# MOS.net
KiCad netlist of a schematic drawn in Altium Designer
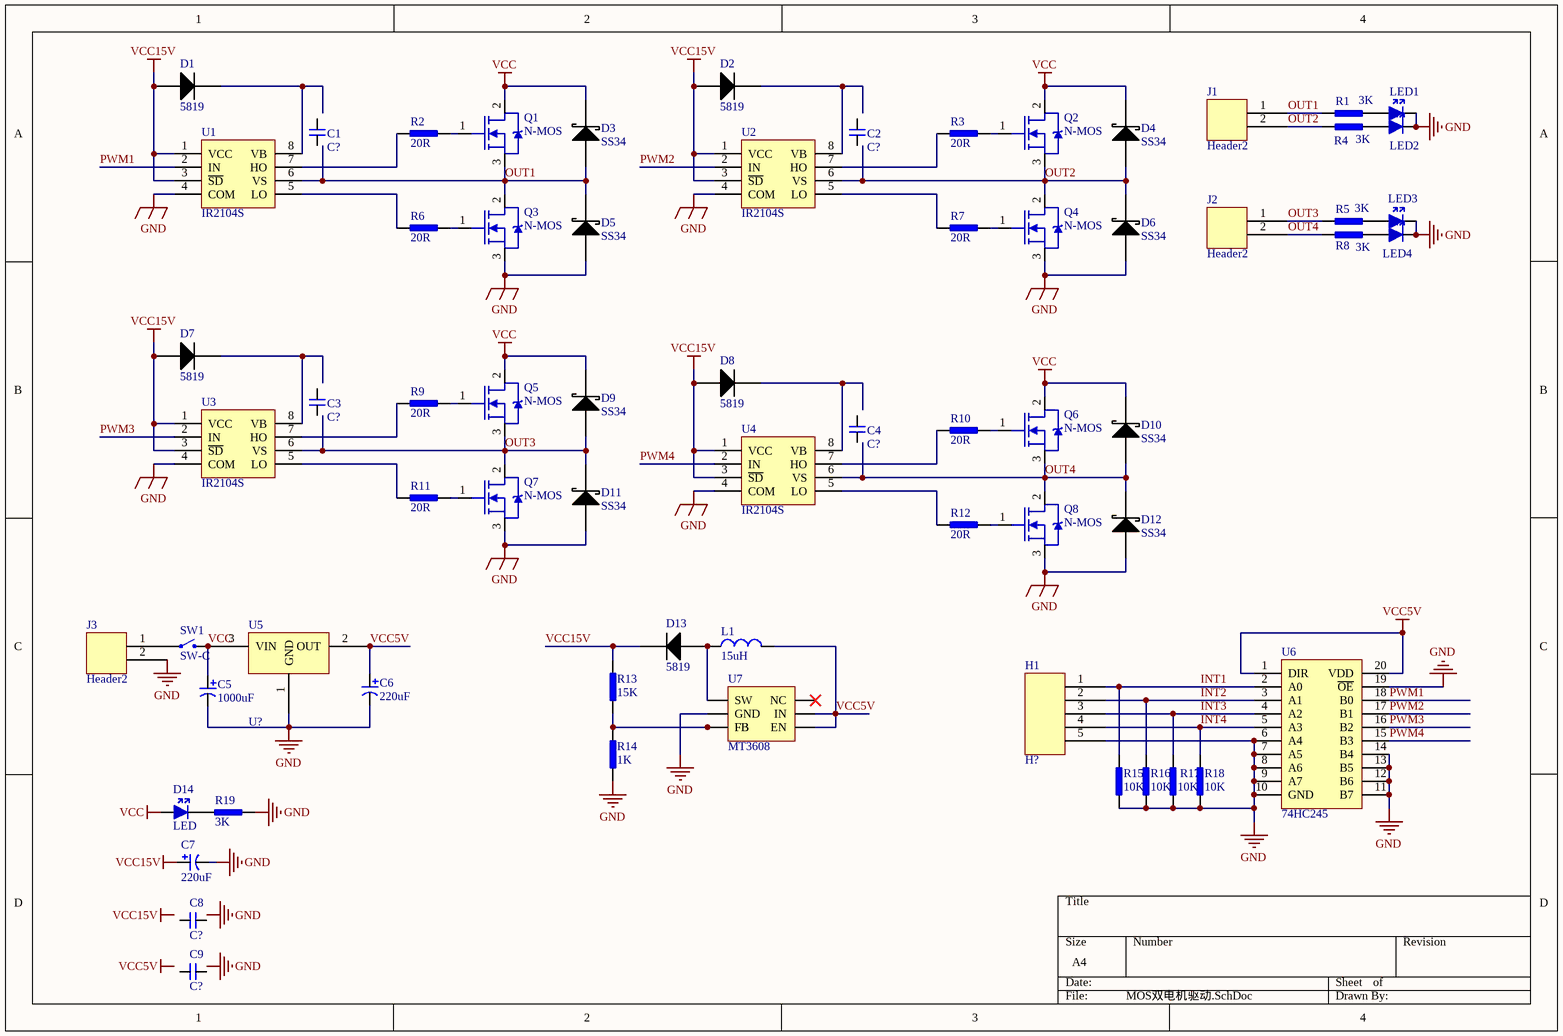
[diagram p0: MOS双电机驱动.SchDoc]

(export (version "E")
  (design (tool "Eeschema 10.0.6"))
  (components
    (comp (ref "C1") (value "C?") (footprint "C 0805") (libsource (lib "常用原理图库") (part "CAP")))
    (comp (ref "C2") (value "C?") (footprint "C 0805") (libsource (lib "常用原理图库") (part "CAP")))
    (comp (ref "C3") (value "C?") (footprint "C 0805") (libsource (lib "常用原理图库") (part "CAP")))
    (comp (ref "C4") (value "C?") (footprint "C 0805") (libsource (lib "常用原理图库") (part "CAP")))
    (comp (ref "C5") (value "1000uF") (footprint "直插电解电容10") (libsource (lib "常用原理图库") (part "CAP-SMD")))
    (comp (ref "C6") (value "220uF") (footprint "CAP6.6X6.6") (libsource (lib "常用原理图库") (part "CAP-SMD")))
    (comp (ref "C7") (value "220uF") (footprint "CAP6.6X6.6") (libsource (lib "常用原理图库") (part "CAP-SMD")))
    (comp (ref "C8") (value "C?") (footprint "C 0805") (libsource (lib "常用原理图库") (part "CAP")))
    (comp (ref "C9") (value "C?") (footprint "C 0805") (libsource (lib "常用原理图库") (part "CAP")))
    (comp (ref "D1") (value "5819") (footprint "D1206") (libsource (lib "MOS电机驱动") (part "D1206")))
    (comp (ref "D2") (value "5819") (footprint "D1206") (libsource (lib "MOS电机驱动") (part "D1206")))
    (comp (ref "D3")
      (value "SS34")
      (footprint "SMA")
      (description "肖特基二极管")
      (libsource (lib "常用原理图库") (part "D-SMA"))
    )
    (comp (ref "D4")
      (value "SS34")
      (footprint "SMA")
      (description "肖特基二极管")
      (libsource (lib "常用原理图库") (part "D-SMA"))
    )
    (comp (ref "D5")
      (value "SS34")
      (footprint "SMA")
      (description "肖特基二极管")
      (libsource (lib "常用原理图库") (part "D-SMA"))
    )
    (comp (ref "D6")
      (value "SS34")
      (footprint "SMA")
      (description "肖特基二极管")
      (libsource (lib "常用原理图库") (part "D-SMA"))
    )
    (comp (ref "D7") (value "5819") (footprint "D1206") (libsource (lib "MOS电机驱动") (part "D1206")))
    (comp (ref "D8") (value "5819") (footprint "D1206") (libsource (lib "MOS电机驱动") (part "D1206")))
    (comp (ref "D9")
      (value "SS34")
      (footprint "SMA")
      (description "肖特基二极管")
      (libsource (lib "常用原理图库") (part "D-SMA"))
    )
    (comp (ref "D10")
      (value "SS34")
      (footprint "SMA")
      (description "肖特基二极管")
      (libsource (lib "常用原理图库") (part "D-SMA"))
    )
    (comp (ref "D11")
      (value "SS34")
      (footprint "SMA")
      (description "肖特基二极管")
      (libsource (lib "常用原理图库") (part "D-SMA"))
    )
    (comp (ref "D12")
      (value "SS34")
      (footprint "SMA")
      (description "肖特基二极管")
      (libsource (lib "常用原理图库") (part "D-SMA"))
    )
    (comp (ref "D13") (value "5819") (footprint "D1206") (libsource (lib "MOS电机驱动") (part "D1206")))
    (comp (ref "D14") (value "LED") (footprint "0805LED") (libsource (lib "常用原理图库") (part "LED")))
    (comp (ref "H1") (value "H?") (footprint "SIP05") (libsource (lib "常用原理图库") (part "header5")))
    (comp (ref "J1") (value "Header2") (footprint "2PIN-5.08B") (libsource (lib "常用原理图库") (part "Header2")))
    (comp (ref "J2") (value "Header2") (footprint "2PIN-5.08B") (libsource (lib "常用原理图库") (part "Header2")))
    (comp (ref "J3") (value "Header2") (footprint "2PIN-5.08B") (libsource (lib "常用原理图库") (part "Header2")))
    (comp (ref "L1") (value "15uH") (footprint "L-06030") (libsource (lib "常用原理图库") (part "Inductance")))
    (comp (ref "LED1") (value "LED") (footprint "0805LED") (libsource (lib "常用原理图库") (part "LED")))
    (comp (ref "LED2") (value "LED") (footprint "0805LED") (libsource (lib "常用原理图库") (part "LED")))
    (comp (ref "LED3") (value "LED") (footprint "0805LED") (libsource (lib "常用原理图库") (part "LED")))
    (comp (ref "LED4") (value "LED") (footprint "0805LED") (libsource (lib "常用原理图库") (part "LED")))
    (comp (ref "Q1") (value "N-MOS") (footprint "常用封装:TO-252") (libsource (lib "常用原理图库") (part "N-MOS")))
    (comp (ref "Q2") (value "N-MOS") (footprint "常用封装:TO-252") (libsource (lib "常用原理图库") (part "N-MOS")))
    (comp (ref "Q3") (value "N-MOS") (footprint "常用封装:TO-252") (libsource (lib "常用原理图库") (part "N-MOS")))
    (comp (ref "Q4") (value "N-MOS") (footprint "常用封装:TO-252") (libsource (lib "常用原理图库") (part "N-MOS")))
    (comp (ref "Q5") (value "N-MOS") (footprint "常用封装:TO-252") (libsource (lib "常用原理图库") (part "N-MOS")))
    (comp (ref "Q6") (value "N-MOS") (footprint "常用封装:TO-252") (libsource (lib "常用原理图库") (part "N-MOS")))
    (comp (ref "Q7") (value "N-MOS") (footprint "常用封装:TO-252") (libsource (lib "常用原理图库") (part "N-MOS")))
    (comp (ref "Q8") (value "N-MOS") (footprint "常用封装:TO-252") (libsource (lib "常用原理图库") (part "N-MOS")))
    (comp (ref "R1") (value "3K") (footprint "R 0805") (libsource (lib "常用原理图库") (part "RES")))
    (comp (ref "R2") (value "20R") (footprint "R 0805") (libsource (lib "常用原理图库") (part "RES")))
    (comp (ref "R3") (value "20R") (footprint "R 0805") (libsource (lib "常用原理图库") (part "RES")))
    (comp (ref "R4") (value "3K") (footprint "R 0805") (libsource (lib "常用原理图库") (part "RES")))
    (comp (ref "R5") (value "3K") (footprint "R 0805") (libsource (lib "常用原理图库") (part "RES")))
    (comp (ref "R6") (value "20R") (footprint "R 0805") (libsource (lib "常用原理图库") (part "RES")))
    (comp (ref "R7") (value "20R") (footprint "R 0805") (libsource (lib "常用原理图库") (part "RES")))
    (comp (ref "R8") (value "3K") (footprint "R 0805") (libsource (lib "常用原理图库") (part "RES")))
    (comp (ref "R9") (value "20R") (footprint "R 0805") (libsource (lib "常用原理图库") (part "RES")))
    (comp (ref "R10") (value "20R") (footprint "R 0805") (libsource (lib "常用原理图库") (part "RES")))
    (comp (ref "R11") (value "20R") (footprint "R 0805") (libsource (lib "常用原理图库") (part "RES")))
    (comp (ref "R12") (value "20R") (footprint "R 0805") (libsource (lib "常用原理图库") (part "RES")))
    (comp (ref "R13") (value "15K") (footprint "R 0805") (libsource (lib "") (part "RES_1")))
    (comp (ref "R14") (value "1K") (footprint "R 0805") (libsource (lib "") (part "RES_1")))
    (comp (ref "R15") (value "10K") (footprint "R 0805") (libsource (lib "") (part "RES_1")))
    (comp (ref "R16") (value "10K") (footprint "R 0805") (libsource (lib "") (part "RES_1")))
    (comp (ref "R17") (value "10K") (footprint "R 0805") (libsource (lib "") (part "RES_1")))
    (comp (ref "R18") (value "10K") (footprint "R 0805") (libsource (lib "") (part "RES_1")))
    (comp (ref "R19") (value "3K") (footprint "R 0805") (libsource (lib "常用原理图库") (part "RES")))
    (comp (ref "SW1") (value "SW-C") (footprint "SW-TO3") (libsource (lib "常用原理图库") (part "SW-C")))
    (comp (ref "U1")
      (value "IR2104S")
      (footprint "SOP-8")
      (description "半桥驱动器")
      (libsource (lib "MOS电机驱动") (part "IR2104S"))
    )
    (comp (ref "U2")
      (value "IR2104S")
      (footprint "SOP-8")
      (description "半桥驱动器")
      (libsource (lib "MOS电机驱动") (part "IR2104S"))
    )
    (comp (ref "U3")
      (value "IR2104S")
      (footprint "SOP-8")
      (description "半桥驱动器")
      (libsource (lib "MOS电机驱动") (part "IR2104S"))
    )
    (comp (ref "U4")
      (value "IR2104S")
      (footprint "SOP-8")
      (description "半桥驱动器")
      (libsource (lib "MOS电机驱动") (part "IR2104S"))
    )
    (comp (ref "U5") (value "U?") (footprint "SOT223") (libsource (lib "常用原理图库") (part "1117")))
    (comp (ref "U6") (value "74HC245") (footprint "TSSOP-20") (libsource (lib "常用原理图库") (part "74HC245")))
    (comp (ref "U7") (value "MT3608") (footprint "SOT23-6") (libsource (lib "常用原理图库") (part "MT3608")))
  )
  (nets
    (net (code "1") (name "/INT1") (class "Default")
      (node (ref "H1") (pin "1") (pintype "passive"))
      (node (ref "R15") (pin "2") (pintype "passive"))
      (node (ref "U6") (pin "2") (pinfunction "A0_2") (pintype "passive"))
    )
    (net (code "2") (name "/INT2") (class "Default")
      (node (ref "H1") (pin "2") (pintype "passive"))
      (node (ref "R16") (pin "2") (pintype "passive"))
      (node (ref "U6") (pin "3") (pinfunction "A1_3") (pintype "passive"))
    )
    (net (code "3") (name "/INT3") (class "Default")
      (node (ref "H1") (pin "3") (pintype "passive"))
      (node (ref "R17") (pin "2") (pintype "passive"))
      (node (ref "U6") (pin "4") (pinfunction "A2_4") (pintype "passive"))
    )
    (net (code "4") (name "/INT4") (class "Default")
      (node (ref "H1") (pin "4") (pintype "passive"))
      (node (ref "R18") (pin "2") (pintype "passive"))
      (node (ref "U6") (pin "5") (pinfunction "A3_5") (pintype "passive"))
    )
    (net (code "5") (name "/OUT1") (class "Default")
      (node (ref "D3") (pin "1") (pinfunction "1_1") (pintype "passive"))
      (node (ref "D5") (pin "2") (pinfunction "2_2") (pintype "passive"))
      (node (ref "J1") (pin "1") (pintype "passive"))
      (node (ref "Q1") (pin "3") (pintype "passive"))
      (node (ref "Q3") (pin "2") (pintype "passive"))
      (node (ref "R1") (pin "1") (pintype "passive"))
      (node (ref "U1") (pin "6") (pinfunction "VS_6") (pintype "passive"))
    )
    (net (code "6") (name "/OUT2") (class "Default")
      (node (ref "D4") (pin "1") (pinfunction "1_1") (pintype "passive"))
      (node (ref "D6") (pin "2") (pinfunction "2_2") (pintype "passive"))
      (node (ref "J1") (pin "2") (pintype "passive"))
      (node (ref "Q2") (pin "3") (pintype "passive"))
      (node (ref "Q4") (pin "2") (pintype "passive"))
      (node (ref "R4") (pin "1") (pintype "passive"))
      (node (ref "U2") (pin "6") (pinfunction "VS_6") (pintype "passive"))
    )
    (net (code "7") (name "/OUT3") (class "Default")
      (node (ref "D11") (pin "2") (pinfunction "2_2") (pintype "passive"))
      (node (ref "D9") (pin "1") (pinfunction "1_1") (pintype "passive"))
      (node (ref "J2") (pin "1") (pintype "passive"))
      (node (ref "Q5") (pin "3") (pintype "passive"))
      (node (ref "Q7") (pin "2") (pintype "passive"))
      (node (ref "R5") (pin "1") (pintype "passive"))
      (node (ref "U3") (pin "6") (pinfunction "VS_6") (pintype "passive"))
    )
    (net (code "8") (name "/OUT4") (class "Default")
      (node (ref "D10") (pin "1") (pinfunction "1_1") (pintype "passive"))
      (node (ref "D12") (pin "2") (pinfunction "2_2") (pintype "passive"))
      (node (ref "J2") (pin "2") (pintype "passive"))
      (node (ref "Q6") (pin "3") (pintype "passive"))
      (node (ref "Q8") (pin "2") (pintype "passive"))
      (node (ref "R8") (pin "1") (pintype "passive"))
      (node (ref "U4") (pin "6") (pinfunction "VS_6") (pintype "passive"))
    )
    (net (code "9") (name "/PWM1") (class "Default")
      (node (ref "U1") (pin "2") (pinfunction "IN_2") (pintype "passive"))
      (node (ref "U6") (pin "18") (pinfunction "B0_18") (pintype "passive"))
    )
    (net (code "10") (name "/PWM2") (class "Default")
      (node (ref "U2") (pin "2") (pinfunction "IN_2") (pintype "passive"))
      (node (ref "U6") (pin "17") (pinfunction "B1_17") (pintype "passive"))
    )
    (net (code "11") (name "/PWM3") (class "Default")
      (node (ref "U3") (pin "2") (pinfunction "IN_2") (pintype "passive"))
      (node (ref "U6") (pin "16") (pinfunction "B2_16") (pintype "passive"))
    )
    (net (code "12") (name "/PWM4") (class "Default")
      (node (ref "U4") (pin "2") (pinfunction "IN_2") (pintype "passive"))
      (node (ref "U6") (pin "15") (pinfunction "B3_15") (pintype "passive"))
    )
    (net (code "13") (name "GND") (class "Default")
      (node (ref "C5") (pin "1") (pintype "passive"))
      (node (ref "C6") (pin "1") (pintype "passive"))
      (node (ref "C7") (pin "1") (pintype "passive"))
      (node (ref "D11") (pin "1") (pinfunction "1_1") (pintype "passive"))
      (node (ref "D12") (pin "1") (pinfunction "1_1") (pintype "passive"))
      (node (ref "D5") (pin "1") (pinfunction "1_1") (pintype "passive"))
      (node (ref "D6") (pin "1") (pinfunction "1_1") (pintype "passive"))
      (node (ref "H1") (pin "5") (pintype "passive"))
      (node (ref "J3") (pin "2") (pintype "passive"))
      (node (ref "LED1") (pin "2") (pintype "passive"))
      (node (ref "LED2") (pin "2") (pintype "passive"))
      (node (ref "LED3") (pin "2") (pintype "passive"))
      (node (ref "LED4") (pin "2") (pintype "passive"))
      (node (ref "Q3") (pin "3") (pintype "passive"))
      (node (ref "Q4") (pin "3") (pintype "passive"))
      (node (ref "Q7") (pin "3") (pintype "passive"))
      (node (ref "Q8") (pin "3") (pintype "passive"))
      (node (ref "R14") (pin "1") (pintype "passive"))
      (node (ref "R15") (pin "1") (pintype "passive"))
      (node (ref "R16") (pin "1") (pintype "passive"))
      (node (ref "R17") (pin "1") (pintype "passive"))
      (node (ref "R18") (pin "1") (pintype "passive"))
      (node (ref "R19") (pin "2") (pintype "passive"))
      (node (ref "U1") (pin "4") (pinfunction "COM_4") (pintype "passive"))
      (node (ref "U2") (pin "4") (pinfunction "COM_4") (pintype "passive"))
      (node (ref "U3") (pin "4") (pinfunction "COM_4") (pintype "passive"))
      (node (ref "U4") (pin "4") (pinfunction "COM_4") (pintype "passive"))
      (node (ref "U5") (pin "1") (pinfunction "GND_1") (pintype "passive"))
      (node (ref "U6") (pin "10") (pinfunction "GND_10") (pintype "passive"))
      (node (ref "U6") (pin "11") (pinfunction "B7_11") (pintype "passive"))
      (node (ref "U6") (pin "12") (pinfunction "B6_12") (pintype "passive"))
      (node (ref "U6") (pin "13") (pinfunction "B5_13") (pintype "passive"))
      (node (ref "U6") (pin "14") (pinfunction "B4_14") (pintype "passive"))
      (node (ref "U6") (pin "19") (pinfunction "~{OE}_19") (pintype "passive"))
      (node (ref "U6") (pin "6") (pinfunction "A4_6") (pintype "passive"))
      (node (ref "U6") (pin "7") (pinfunction "A5_7") (pintype "passive"))
      (node (ref "U6") (pin "8") (pinfunction "A6_8") (pintype "passive"))
      (node (ref "U6") (pin "9") (pinfunction "A7_9") (pintype "passive"))
      (node (ref "U7") (pin "2") (pinfunction "GND_2") (pintype "passive"))
    )
    (net (code "14") (name "Net-(D14-Pad2)") (class "Default")
      (node (ref "D14") (pin "2") (pintype "passive"))
      (node (ref "R19") (pin "1") (pintype "passive"))
    )
    (net (code "15") (name "Net-(J3-Pad1)") (class "Default")
      (node (ref "J3") (pin "1") (pintype "passive"))
      (node (ref "SW1") (pin "1") (pintype "passive"))
    )
    (net (code "16") (name "Net-(LED1-Pad1)") (class "Default")
      (node (ref "LED1") (pin "1") (pintype "passive"))
      (node (ref "R1") (pin "2") (pintype "passive"))
    )
    (net (code "17") (name "Net-(LED2-Pad1)") (class "Default")
      (node (ref "LED2") (pin "1") (pintype "passive"))
      (node (ref "R4") (pin "2") (pintype "passive"))
    )
    (net (code "18") (name "Net-(LED3-Pad1)") (class "Default")
      (node (ref "LED3") (pin "1") (pintype "passive"))
      (node (ref "R5") (pin "2") (pintype "passive"))
    )
    (net (code "19") (name "Net-(LED4-Pad1)") (class "Default")
      (node (ref "LED4") (pin "1") (pintype "passive"))
      (node (ref "R8") (pin "2") (pintype "passive"))
    )
    (net (code "20") (name "Net-(Q1-Pad1)") (class "Default")
      (node (ref "Q1") (pin "1") (pintype "passive"))
      (node (ref "R2") (pin "2") (pintype "passive"))
    )
    (net (code "21") (name "Net-(Q2-Pad1)") (class "Default")
      (node (ref "Q2") (pin "1") (pintype "passive"))
      (node (ref "R3") (pin "2") (pintype "passive"))
    )
    (net (code "22") (name "Net-(Q3-Pad1)") (class "Default")
      (node (ref "Q3") (pin "1") (pintype "passive"))
      (node (ref "R6") (pin "2") (pintype "passive"))
    )
    (net (code "23") (name "Net-(Q4-Pad1)") (class "Default")
      (node (ref "Q4") (pin "1") (pintype "passive"))
      (node (ref "R7") (pin "2") (pintype "passive"))
    )
    (net (code "24") (name "Net-(Q5-Pad1)") (class "Default")
      (node (ref "Q5") (pin "1") (pintype "passive"))
      (node (ref "R9") (pin "2") (pintype "passive"))
    )
    (net (code "25") (name "Net-(Q6-Pad1)") (class "Default")
      (node (ref "Q6") (pin "1") (pintype "passive"))
      (node (ref "R10") (pin "2") (pintype "passive"))
    )
    (net (code "26") (name "Net-(Q7-Pad1)") (class "Default")
      (node (ref "Q7") (pin "1") (pintype "passive"))
      (node (ref "R11") (pin "2") (pintype "passive"))
    )
    (net (code "27") (name "Net-(Q8-Pad1)") (class "Default")
      (node (ref "Q8") (pin "1") (pintype "passive"))
      (node (ref "R12") (pin "2") (pintype "passive"))
    )
    (net (code "28") (name "Net-(R13-Pad1)") (class "Default")
      (node (ref "R13") (pin "1") (pintype "passive"))
      (node (ref "R14") (pin "2") (pintype "passive"))
      (node (ref "U7") (pin "3") (pinfunction "FB_3") (pintype "passive"))
      (node (ref "U7") (pin "4") (pinfunction "FB_4") (pintype "passive"))
    )
    (net (code "29") (name "Net-(U1-HO)") (class "Default")
      (node (ref "R2") (pin "1") (pintype "passive"))
      (node (ref "U1") (pin "7") (pinfunction "HO_7") (pintype "passive"))
    )
    (net (code "30") (name "Net-(U1-LO)") (class "Default")
      (node (ref "R6") (pin "1") (pintype "passive"))
      (node (ref "U1") (pin "5") (pinfunction "LO_5") (pintype "passive"))
    )
    (net (code "31") (name "Net-(U1-VB)") (class "Default")
      (node (ref "D1") (pin "2") (pinfunction "2_2") (pintype "passive"))
      (node (ref "U1") (pin "8") (pinfunction "VB_8") (pintype "passive"))
    )
    (net (code "32") (name "Net-(U2-HO)") (class "Default")
      (node (ref "R3") (pin "1") (pintype "passive"))
      (node (ref "U2") (pin "7") (pinfunction "HO_7") (pintype "passive"))
    )
    (net (code "33") (name "Net-(U2-LO)") (class "Default")
      (node (ref "R7") (pin "1") (pintype "passive"))
      (node (ref "U2") (pin "5") (pinfunction "LO_5") (pintype "passive"))
    )
    (net (code "34") (name "Net-(U2-VB)") (class "Default")
      (node (ref "D2") (pin "2") (pinfunction "2_2") (pintype "passive"))
      (node (ref "U2") (pin "8") (pinfunction "VB_8") (pintype "passive"))
    )
    (net (code "35") (name "Net-(U3-HO)") (class "Default")
      (node (ref "R9") (pin "1") (pintype "passive"))
      (node (ref "U3") (pin "7") (pinfunction "HO_7") (pintype "passive"))
    )
    (net (code "36") (name "Net-(U3-LO)") (class "Default")
      (node (ref "R11") (pin "1") (pintype "passive"))
      (node (ref "U3") (pin "5") (pinfunction "LO_5") (pintype "passive"))
    )
    (net (code "37") (name "Net-(U3-VB)") (class "Default")
      (node (ref "D7") (pin "2") (pinfunction "2_2") (pintype "passive"))
      (node (ref "U3") (pin "8") (pinfunction "VB_8") (pintype "passive"))
    )
    (net (code "38") (name "Net-(U4-HO)") (class "Default")
      (node (ref "R10") (pin "1") (pintype "passive"))
      (node (ref "U4") (pin "7") (pinfunction "HO_7") (pintype "passive"))
    )
    (net (code "39") (name "Net-(U4-LO)") (class "Default")
      (node (ref "R12") (pin "1") (pintype "passive"))
      (node (ref "U4") (pin "5") (pinfunction "LO_5") (pintype "passive"))
    )
    (net (code "40") (name "Net-(U4-VB)") (class "Default")
      (node (ref "D8") (pin "2") (pinfunction "2_2") (pintype "passive"))
      (node (ref "U4") (pin "8") (pinfunction "VB_8") (pintype "passive"))
    )
    (net (code "41") (name "Net-(U7-SW)") (class "Default")
      (node (ref "D13") (pin "1") (pinfunction "1_1") (pintype "passive"))
      (node (ref "L1") (pin "2") (pinfunction "2_2") (pintype "passive"))
      (node (ref "U7") (pin "1") (pinfunction "SW_1") (pintype "passive"))
    )
    (net (code "42") (name "VCC") (class "Default")
      (node (ref "C5") (pin "2") (pintype "passive"))
      (node (ref "D10") (pin "2") (pinfunction "2_2") (pintype "passive"))
      (node (ref "D14") (pin "1") (pintype "passive"))
      (node (ref "D3") (pin "2") (pinfunction "2_2") (pintype "passive"))
      (node (ref "D4") (pin "2") (pinfunction "2_2") (pintype "passive"))
      (node (ref "D9") (pin "2") (pinfunction "2_2") (pintype "passive"))
      (node (ref "Q1") (pin "2") (pintype "passive"))
      (node (ref "Q2") (pin "2") (pintype "passive"))
      (node (ref "Q5") (pin "2") (pintype "passive"))
      (node (ref "Q6") (pin "2") (pintype "passive"))
      (node (ref "SW1") (pin "2") (pintype "passive"))
      (node (ref "U5") (pin "3") (pinfunction "VIN_3") (pintype "passive"))
    )
    (net (code "43") (name "VCC5V") (class "Default")
      (node (ref "C6") (pin "2") (pintype "passive"))
      (node (ref "L1") (pin "1") (pinfunction "1_1") (pintype "passive"))
      (node (ref "U5") (pin "2") (pinfunction "OUT_2") (pintype "passive"))
      (node (ref "U6") (pin "1") (pinfunction "DIR_1") (pintype "passive"))
      (node (ref "U6") (pin "20") (pinfunction "VDD_20") (pintype "passive"))
      (node (ref "U7") (pin "4") (pinfunction "EN_4") (pintype "passive"))
      (node (ref "U7") (pin "5") (pinfunction "IN_5") (pintype "passive"))
    )
    (net (code "44") (name "VCC15V") (class "Default")
      (node (ref "C7") (pin "2") (pintype "passive"))
      (node (ref "D1") (pin "1") (pinfunction "1_1") (pintype "passive"))
      (node (ref "D13") (pin "2") (pinfunction "2_2") (pintype "passive"))
      (node (ref "D2") (pin "1") (pinfunction "1_1") (pintype "passive"))
      (node (ref "D7") (pin "1") (pinfunction "1_1") (pintype "passive"))
      (node (ref "D8") (pin "1") (pinfunction "1_1") (pintype "passive"))
      (node (ref "R13") (pin "2") (pintype "passive"))
      (node (ref "U1") (pin "1") (pinfunction "VCC_1") (pintype "passive"))
      (node (ref "U1") (pin "3") (pinfunction "~{SD}_3") (pintype "passive"))
      (node (ref "U2") (pin "1") (pinfunction "VCC_1") (pintype "passive"))
      (node (ref "U2") (pin "3") (pinfunction "~{SD}_3") (pintype "passive"))
      (node (ref "U3") (pin "1") (pinfunction "VCC_1") (pintype "passive"))
      (node (ref "U3") (pin "3") (pinfunction "~{SD}_3") (pintype "passive"))
      (node (ref "U4") (pin "1") (pinfunction "VCC_1") (pintype "passive"))
      (node (ref "U4") (pin "3") (pinfunction "~{SD}_3") (pintype "passive"))
    )
    (net (code "45") (name "unconnected-(C1-Pad1)") (class "Default")
      (node (ref "C1") (pin "1") (pintype "passive"))
    )
    (net (code "46") (name "unconnected-(C1-Pad2)") (class "Default")
      (node (ref "C1") (pin "2") (pintype "passive"))
    )
    (net (code "47") (name "unconnected-(C2-Pad1)") (class "Default")
      (node (ref "C2") (pin "1") (pintype "passive"))
    )
    (net (code "48") (name "unconnected-(C2-Pad2)") (class "Default")
      (node (ref "C2") (pin "2") (pintype "passive"))
    )
    (net (code "49") (name "unconnected-(C3-Pad1)") (class "Default")
      (node (ref "C3") (pin "1") (pintype "passive"))
    )
    (net (code "50") (name "unconnected-(C3-Pad2)") (class "Default")
      (node (ref "C3") (pin "2") (pintype "passive"))
    )
    (net (code "51") (name "unconnected-(C4-Pad1)") (class "Default")
      (node (ref "C4") (pin "1") (pintype "passive"))
    )
    (net (code "52") (name "unconnected-(C4-Pad2)") (class "Default")
      (node (ref "C4") (pin "2") (pintype "passive"))
    )
    (net (code "53") (name "unconnected-(C8-Pad1)") (class "Default")
      (node (ref "C8") (pin "1") (pintype "passive"))
    )
    (net (code "54") (name "unconnected-(C8-Pad2)") (class "Default")
      (node (ref "C8") (pin "2") (pintype "passive"))
    )
    (net (code "55") (name "unconnected-(C9-Pad1)") (class "Default")
      (node (ref "C9") (pin "1") (pintype "passive"))
    )
    (net (code "56") (name "unconnected-(C9-Pad2)") (class "Default")
      (node (ref "C9") (pin "2") (pintype "passive"))
    )
    (net (code "57") (name "unconnected-(U7-NC-Pad6)") (class "Default")
      (node (ref "U7") (pin "6") (pinfunction "NC_6") (pintype "passive+no_connect"))
    )
  )
)
